# Computation.net
KiCad netlist of a schematic drawn in Altium Designer
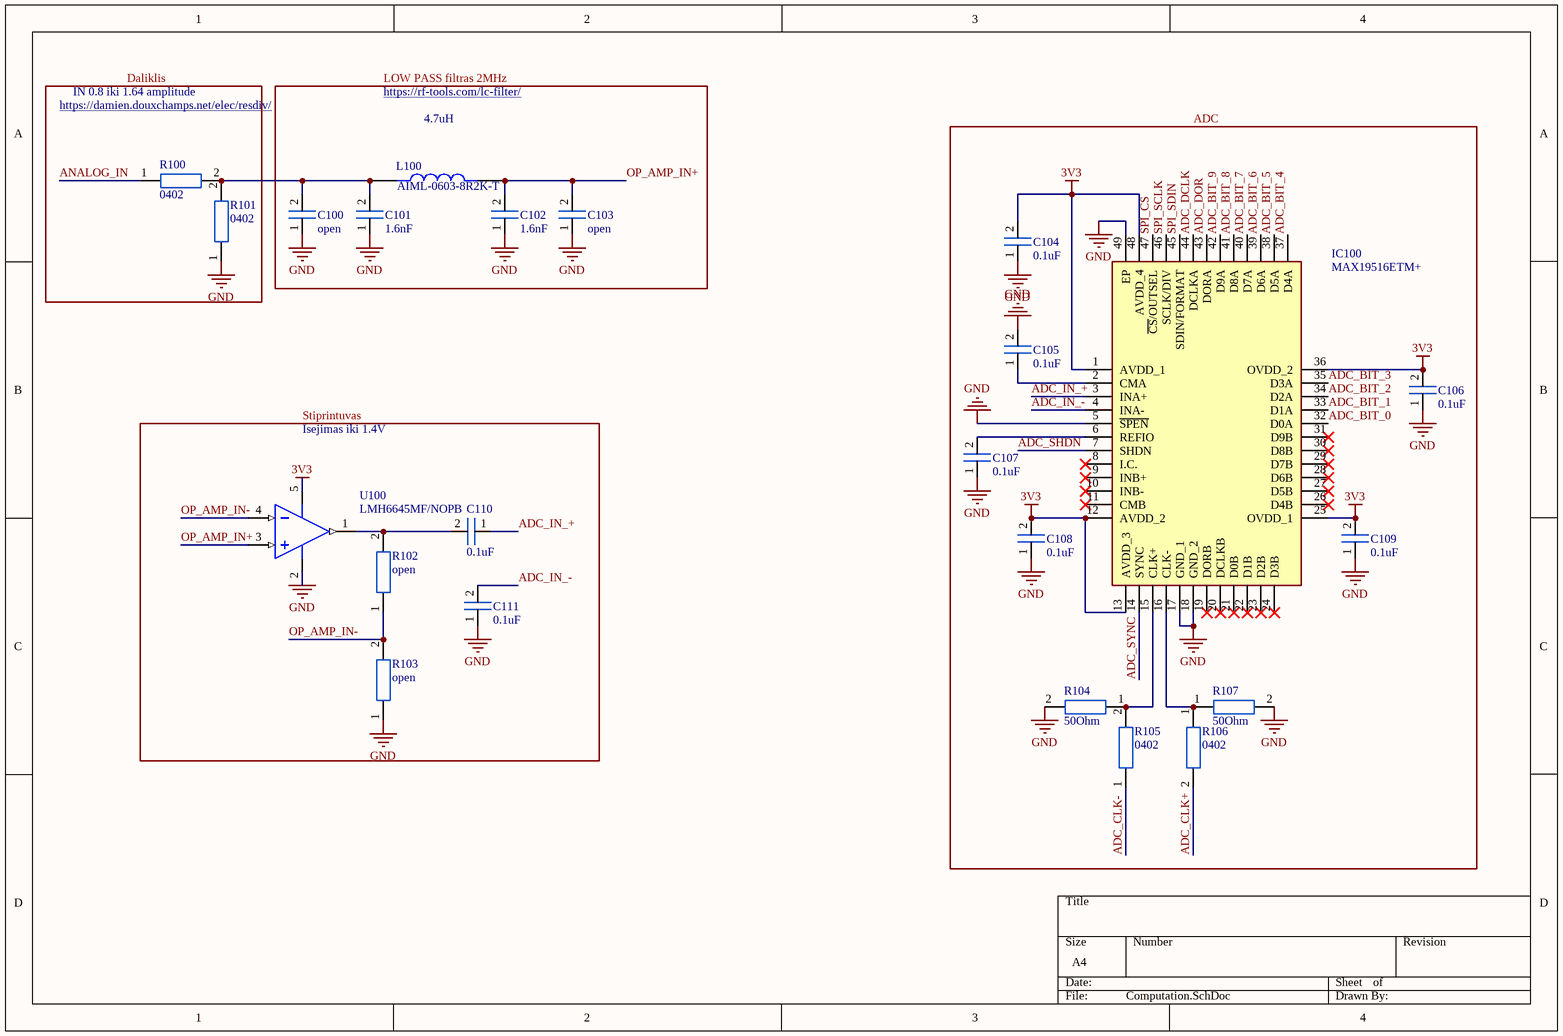
[diagram p0: Computation.SchDoc]

(export (version "E")
  (design (tool "Eeschema 10.0.6"))
  (components
    (comp (ref "C100")
      (value "open")
      (footprint "0402_footprint")
      (description "0402 capacitor")
      (libsource (lib "Schlib1") (part "Capacitor_0402"))
    )
    (comp (ref "C101")
      (value "1.6nF")
      (footprint "0402_footprint")
      (description "0402 capacitor")
      (libsource (lib "Schlib1") (part "Capacitor_0402"))
    )
    (comp (ref "C102")
      (value "1.6nF")
      (footprint "0402_footprint")
      (description "0402 capacitor")
      (libsource (lib "Schlib1") (part "Capacitor_0402"))
    )
    (comp (ref "C103")
      (value "open")
      (footprint "0402_footprint")
      (description "0402 capacitor")
      (libsource (lib "Schlib1") (part "Capacitor_0402"))
    )
    (comp (ref "C104")
      (value "0.1uF")
      (footprint "0402_footprint")
      (description "0402 capacitor")
      (libsource (lib "Schlib1") (part "Capacitor_0402"))
    )
    (comp (ref "C105")
      (value "0.1uF")
      (footprint "0402_footprint")
      (description "0402 capacitor")
      (libsource (lib "Schlib1") (part "Capacitor_0402"))
    )
    (comp (ref "C106")
      (value "0.1uF")
      (footprint "0402_footprint")
      (description "0402 capacitor")
      (libsource (lib "Schlib1") (part "Capacitor_0402"))
    )
    (comp (ref "C107")
      (value "0.1uF")
      (footprint "0402_footprint")
      (description "0402 capacitor")
      (libsource (lib "Schlib1") (part "Capacitor_0402"))
    )
    (comp (ref "C108")
      (value "0.1uF")
      (footprint "0402_footprint")
      (description "0402 capacitor")
      (libsource (lib "Schlib1") (part "Capacitor_0402"))
    )
    (comp (ref "C109")
      (value "0.1uF")
      (footprint "0402_footprint")
      (description "0402 capacitor")
      (libsource (lib "Schlib1") (part "Capacitor_0402"))
    )
    (comp (ref "C110")
      (value "0.1uF")
      (footprint "0402_footprint")
      (description "0402 capacitor")
      (libsource (lib "Schlib1") (part "Capacitor_0402"))
    )
    (comp (ref "C111")
      (value "0.1uF")
      (footprint "0402_footprint")
      (description "0402 capacitor")
      (libsource (lib "Schlib1") (part "Capacitor_0402"))
    )
    (comp (ref "IC100")
      (value "MAX19516ETM+")
      (footprint "SamacSys:QFN50P700X700X80-49N")
      (description "Integrated Circuit")
      (fields (field (name "MOUSER PART NUMBER") "700-MAX19516ETM"))
      (libsource (lib "*") (part "MAX19516ETM+"))
    )
    (comp (ref "L100")
      (value "AIML-0603-8R2K-T")
      (footprint "INDC1608X95N")
      (description "8.2 ÂµH Shielded Multilayer Inductor 4 mA 2.1Ohm Max 0603 (1608 Metric)")
      (fields (field (name "MF") "Abracon"))
      (libsource (lib "AIML-0603-8R2K-T") (part "AIML-0603-8R2K-T"))
    )
    (comp (ref "R100")
      (value "0402")
      (footprint "0402_footprint")
      (libsource (lib "Schlib1") (part "Resistor_0402"))
    )
    (comp (ref "R101")
      (value "0402")
      (footprint "0402_footprint")
      (libsource (lib "Schlib1") (part "Resistor_0402"))
    )
    (comp (ref "R102")
      (value "open")
      (footprint "0402_footprint")
      (libsource (lib "Schlib1") (part "Resistor_0402"))
    )
    (comp (ref "R103")
      (value "open")
      (footprint "0402_footprint")
      (libsource (lib "Schlib1") (part "Resistor_0402"))
    )
    (comp (ref "R104")
      (value "50Ohm")
      (footprint "0402_footprint")
      (libsource (lib "Schlib1") (part "Resistor_0402"))
    )
    (comp (ref "R105")
      (value "0402")
      (footprint "0402_footprint")
      (libsource (lib "Schlib1") (part "Resistor_0402"))
    )
    (comp (ref "R106")
      (value "0402")
      (footprint "0402_footprint")
      (libsource (lib "Schlib1") (part "Resistor_0402"))
    )
    (comp (ref "R107")
      (value "50Ohm")
      (footprint "0402_footprint")
      (libsource (lib "Schlib1") (part "Resistor_0402"))
    )
    (comp (ref "U100")
      (value "LMH6645MF/NOPB")
      (footprint "DBV0005A_N")
      (fields (field (name "MANUFACTURER") "Texas Instruments"))
      (libsource (lib "Altium Content Vault") (part "AMP-OPA-LM7121-5"))
    )
  )
  (nets
    (net (code "1") (name "/ADC_BIT_0") (class "Default")
      (node (ref "IC100") (pin "32") (pinfunction "D0A_32") (pintype "passive"))
    )
    (net (code "2") (name "/ADC_BIT_1") (class "Default")
      (node (ref "IC100") (pin "33") (pinfunction "D1A_33") (pintype "passive"))
    )
    (net (code "3") (name "/ADC_BIT_2") (class "Default")
      (node (ref "IC100") (pin "34") (pinfunction "D2A_34") (pintype "passive"))
    )
    (net (code "4") (name "/ADC_BIT_3") (class "Default")
      (node (ref "IC100") (pin "35") (pinfunction "D3A_35") (pintype "passive"))
    )
    (net (code "5") (name "/ADC_BIT_4") (class "Default")
      (node (ref "IC100") (pin "37") (pinfunction "D4A_37") (pintype "passive"))
    )
    (net (code "6") (name "/ADC_BIT_5") (class "Default")
      (node (ref "IC100") (pin "38") (pinfunction "D5A_38") (pintype "passive"))
    )
    (net (code "7") (name "/ADC_BIT_6") (class "Default")
      (node (ref "IC100") (pin "39") (pinfunction "D6A_39") (pintype "passive"))
    )
    (net (code "8") (name "/ADC_BIT_7") (class "Default")
      (node (ref "IC100") (pin "40") (pinfunction "D7A_40") (pintype "passive"))
    )
    (net (code "9") (name "/ADC_BIT_8") (class "Default")
      (node (ref "IC100") (pin "41") (pinfunction "D8A_41") (pintype "passive"))
    )
    (net (code "10") (name "/ADC_BIT_9") (class "Default")
      (node (ref "IC100") (pin "42") (pinfunction "D9A_42") (pintype "passive"))
    )
    (net (code "11") (name "/ADC_CLK+") (class "Default")
      (node (ref "R106") (pin "2") (pinfunction "2_2") (pintype "passive"))
    )
    (net (code "12") (name "/ADC_CLK-") (class "Default")
      (node (ref "R105") (pin "1") (pinfunction "1_1") (pintype "passive"))
    )
    (net (code "13") (name "/ADC_DCLK") (class "Default")
      (node (ref "IC100") (pin "44") (pinfunction "DCLKA_44") (pintype "passive"))
    )
    (net (code "14") (name "/ADC_DOR") (class "Default")
      (node (ref "IC100") (pin "43") (pinfunction "DORA_43") (pintype "passive"))
    )
    (net (code "15") (name "/ADC_IN_+") (class "Default")
      (node (ref "C110") (pin "1") (pinfunction "1_1") (pintype "passive"))
      (node (ref "IC100") (pin "3") (pinfunction "INA+_3") (pintype "passive"))
    )
    (net (code "16") (name "/ADC_IN_-") (class "Default")
      (node (ref "C111") (pin "2") (pinfunction "2_2") (pintype "passive"))
      (node (ref "IC100") (pin "4") (pinfunction "INA-_4") (pintype "passive"))
    )
    (net (code "17") (name "/ADC_SHDN") (class "Default")
      (node (ref "IC100") (pin "7") (pinfunction "SHDN_7") (pintype "passive"))
    )
    (net (code "18") (name "/ADC_SYNC") (class "Default")
      (node (ref "IC100") (pin "14") (pinfunction "SYNC_14") (pintype "passive"))
    )
    (net (code "19") (name "/ANALOG_IN") (class "Default")
      (node (ref "R100") (pin "1") (pinfunction "1_1") (pintype "passive"))
    )
    (net (code "20") (name "/OP_AMP_IN+") (class "Default")
      (node (ref "C102") (pin "2") (pinfunction "2_2") (pintype "passive"))
      (node (ref "C103") (pin "2") (pinfunction "2_2") (pintype "passive"))
      (node (ref "L100") (pin "2") (pinfunction "2_2") (pintype "passive"))
      (node (ref "U100") (pin "3") (pinfunction "IN+_3") (pintype "input"))
    )
    (net (code "21") (name "/OP_AMP_IN-") (class "Default")
      (node (ref "R102") (pin "1") (pinfunction "1_1") (pintype "passive"))
      (node (ref "R103") (pin "2") (pinfunction "2_2") (pintype "passive"))
      (node (ref "U100") (pin "4") (pinfunction "IN-_4") (pintype "input"))
    )
    (net (code "22") (name "/SPI_CS") (class "Default")
      (node (ref "IC100") (pin "47") (pinfunction "~{CS}/OUTSEL_47") (pintype "passive"))
    )
    (net (code "23") (name "/SPI_SCLK") (class "Default")
      (node (ref "IC100") (pin "46") (pinfunction "SCLK/DIV_46") (pintype "passive"))
    )
    (net (code "24") (name "/SPI_SDIN") (class "Default")
      (node (ref "IC100") (pin "45") (pinfunction "SDIN/FORMAT_45") (pintype "passive"))
    )
    (net (code "25") (name "3V3") (class "Default")
      (node (ref "C104") (pin "2") (pinfunction "2_2") (pintype "passive"))
      (node (ref "C106") (pin "2") (pinfunction "2_2") (pintype "passive"))
      (node (ref "C108") (pin "2") (pinfunction "2_2") (pintype "passive"))
      (node (ref "C109") (pin "2") (pinfunction "2_2") (pintype "passive"))
      (node (ref "IC100") (pin "1") (pinfunction "AVDD_1_1") (pintype "passive"))
      (node (ref "IC100") (pin "12") (pinfunction "AVDD_2_12") (pintype "passive"))
      (node (ref "IC100") (pin "13") (pinfunction "AVDD_3_13") (pintype "passive"))
      (node (ref "IC100") (pin "25") (pinfunction "OVDD_1_25") (pintype "passive"))
      (node (ref "IC100") (pin "36") (pinfunction "OVDD_2_36") (pintype "passive"))
      (node (ref "IC100") (pin "48") (pinfunction "AVDD_4_48") (pintype "passive"))
      (node (ref "U100") (pin "5") (pinfunction "V+_5") (pintype "power_in"))
    )
    (net (code "26") (name "GND") (class "Default")
      (node (ref "C100") (pin "1") (pinfunction "1_1") (pintype "passive"))
      (node (ref "C101") (pin "1") (pinfunction "1_1") (pintype "passive"))
      (node (ref "C102") (pin "1") (pinfunction "1_1") (pintype "passive"))
      (node (ref "C103") (pin "1") (pinfunction "1_1") (pintype "passive"))
      (node (ref "C104") (pin "1") (pinfunction "1_1") (pintype "passive"))
      (node (ref "C105") (pin "2") (pinfunction "2_2") (pintype "passive"))
      (node (ref "C106") (pin "1") (pinfunction "1_1") (pintype "passive"))
      (node (ref "C107") (pin "1") (pinfunction "1_1") (pintype "passive"))
      (node (ref "C108") (pin "1") (pinfunction "1_1") (pintype "passive"))
      (node (ref "C109") (pin "1") (pinfunction "1_1") (pintype "passive"))
      (node (ref "C111") (pin "1") (pinfunction "1_1") (pintype "passive"))
      (node (ref "IC100") (pin "17") (pinfunction "GND_1_17") (pintype "passive"))
      (node (ref "IC100") (pin "18") (pinfunction "GND_2_18") (pintype "passive"))
      (node (ref "IC100") (pin "49") (pinfunction "EP_49") (pintype "passive"))
      (node (ref "IC100") (pin "5") (pinfunction "~{SPEN}_5") (pintype "passive"))
      (node (ref "R101") (pin "1") (pinfunction "1_1") (pintype "passive"))
      (node (ref "R103") (pin "1") (pinfunction "1_1") (pintype "passive"))
      (node (ref "R104") (pin "2") (pinfunction "2_2") (pintype "passive"))
      (node (ref "R107") (pin "2") (pinfunction "2_2") (pintype "passive"))
      (node (ref "U100") (pin "2") (pinfunction "V-_2") (pintype "power_in"))
    )
    (net (code "27") (name "Net-(C100-Pad2)") (class "Default")
      (node (ref "C100") (pin "2") (pinfunction "2_2") (pintype "passive"))
      (node (ref "C101") (pin "2") (pinfunction "2_2") (pintype "passive"))
      (node (ref "L100") (pin "1") (pinfunction "1_1") (pintype "passive"))
      (node (ref "R100") (pin "2") (pinfunction "2_2") (pintype "passive"))
      (node (ref "R101") (pin "2") (pinfunction "2_2") (pintype "passive"))
    )
    (net (code "28") (name "Net-(IC100-CLK+)") (class "Default")
      (node (ref "IC100") (pin "15") (pinfunction "CLK+_15") (pintype "passive"))
      (node (ref "R104") (pin "1") (pinfunction "1_1") (pintype "passive"))
      (node (ref "R105") (pin "2") (pinfunction "2_2") (pintype "passive"))
    )
    (net (code "29") (name "Net-(IC100-CLK-)") (class "Default")
      (node (ref "IC100") (pin "16") (pinfunction "CLK-_16") (pintype "passive"))
      (node (ref "R106") (pin "1") (pinfunction "1_1") (pintype "passive"))
      (node (ref "R107") (pin "1") (pinfunction "1_1") (pintype "passive"))
    )
    (net (code "30") (name "Net-(IC100-CMA)") (class "Default")
      (node (ref "C105") (pin "1") (pinfunction "1_1") (pintype "passive"))
      (node (ref "IC100") (pin "2") (pinfunction "CMA_2") (pintype "passive"))
    )
    (net (code "31") (name "Net-(IC100-REFIO)") (class "Default")
      (node (ref "C107") (pin "2") (pinfunction "2_2") (pintype "passive"))
      (node (ref "IC100") (pin "6") (pinfunction "REFIO_6") (pintype "passive"))
    )
    (net (code "32") (name "Net-(U100-OUT)") (class "Default")
      (node (ref "C110") (pin "2") (pinfunction "2_2") (pintype "passive"))
      (node (ref "R102") (pin "2") (pinfunction "2_2") (pintype "passive"))
      (node (ref "U100") (pin "1") (pinfunction "OUT_1") (pintype "output"))
    )
    (net (code "33") (name "unconnected-(IC100-CMB-Pad11)") (class "Default")
      (node (ref "IC100") (pin "11") (pinfunction "CMB_11") (pintype "passive+no_connect"))
    )
    (net (code "34") (name "unconnected-(IC100-D0B-Pad21)") (class "Default")
      (node (ref "IC100") (pin "21") (pinfunction "D0B_21") (pintype "passive+no_connect"))
    )
    (net (code "35") (name "unconnected-(IC100-D1B-Pad22)") (class "Default")
      (node (ref "IC100") (pin "22") (pinfunction "D1B_22") (pintype "passive+no_connect"))
    )
    (net (code "36") (name "unconnected-(IC100-D2B-Pad23)") (class "Default")
      (node (ref "IC100") (pin "23") (pinfunction "D2B_23") (pintype "passive+no_connect"))
    )
    (net (code "37") (name "unconnected-(IC100-D3B-Pad24)") (class "Default")
      (node (ref "IC100") (pin "24") (pinfunction "D3B_24") (pintype "passive+no_connect"))
    )
    (net (code "38") (name "unconnected-(IC100-D4B-Pad26)") (class "Default")
      (node (ref "IC100") (pin "26") (pinfunction "D4B_26") (pintype "passive+no_connect"))
    )
    (net (code "39") (name "unconnected-(IC100-D5B-Pad27)") (class "Default")
      (node (ref "IC100") (pin "27") (pinfunction "D5B_27") (pintype "passive+no_connect"))
    )
    (net (code "40") (name "unconnected-(IC100-D6B-Pad28)") (class "Default")
      (node (ref "IC100") (pin "28") (pinfunction "D6B_28") (pintype "passive+no_connect"))
    )
    (net (code "41") (name "unconnected-(IC100-D7B-Pad29)") (class "Default")
      (node (ref "IC100") (pin "29") (pinfunction "D7B_29") (pintype "passive+no_connect"))
    )
    (net (code "42") (name "unconnected-(IC100-D8B-Pad30)") (class "Default")
      (node (ref "IC100") (pin "30") (pinfunction "D8B_30") (pintype "passive+no_connect"))
    )
    (net (code "43") (name "unconnected-(IC100-D9B-Pad31)") (class "Default")
      (node (ref "IC100") (pin "31") (pinfunction "D9B_31") (pintype "passive+no_connect"))
    )
    (net (code "44") (name "unconnected-(IC100-DCLKB-Pad20)") (class "Default")
      (node (ref "IC100") (pin "20") (pinfunction "DCLKB_20") (pintype "passive+no_connect"))
    )
    (net (code "45") (name "unconnected-(IC100-DORB-Pad19)") (class "Default")
      (node (ref "IC100") (pin "19") (pinfunction "DORB_19") (pintype "passive+no_connect"))
    )
    (net (code "46") (name "unconnected-(IC100-I.C.-Pad8)") (class "Default")
      (node (ref "IC100") (pin "8") (pinfunction "I.C._8") (pintype "passive+no_connect"))
    )
    (net (code "47") (name "unconnected-(IC100-INB+-Pad9)") (class "Default")
      (node (ref "IC100") (pin "9") (pinfunction "INB+_9") (pintype "passive+no_connect"))
    )
    (net (code "48") (name "unconnected-(IC100-INB--Pad10)") (class "Default")
      (node (ref "IC100") (pin "10") (pinfunction "INB-_10") (pintype "passive+no_connect"))
    )
  )
)
